# BMS_Main.net
KiCad netlist of a schematic drawn in Altium Designer
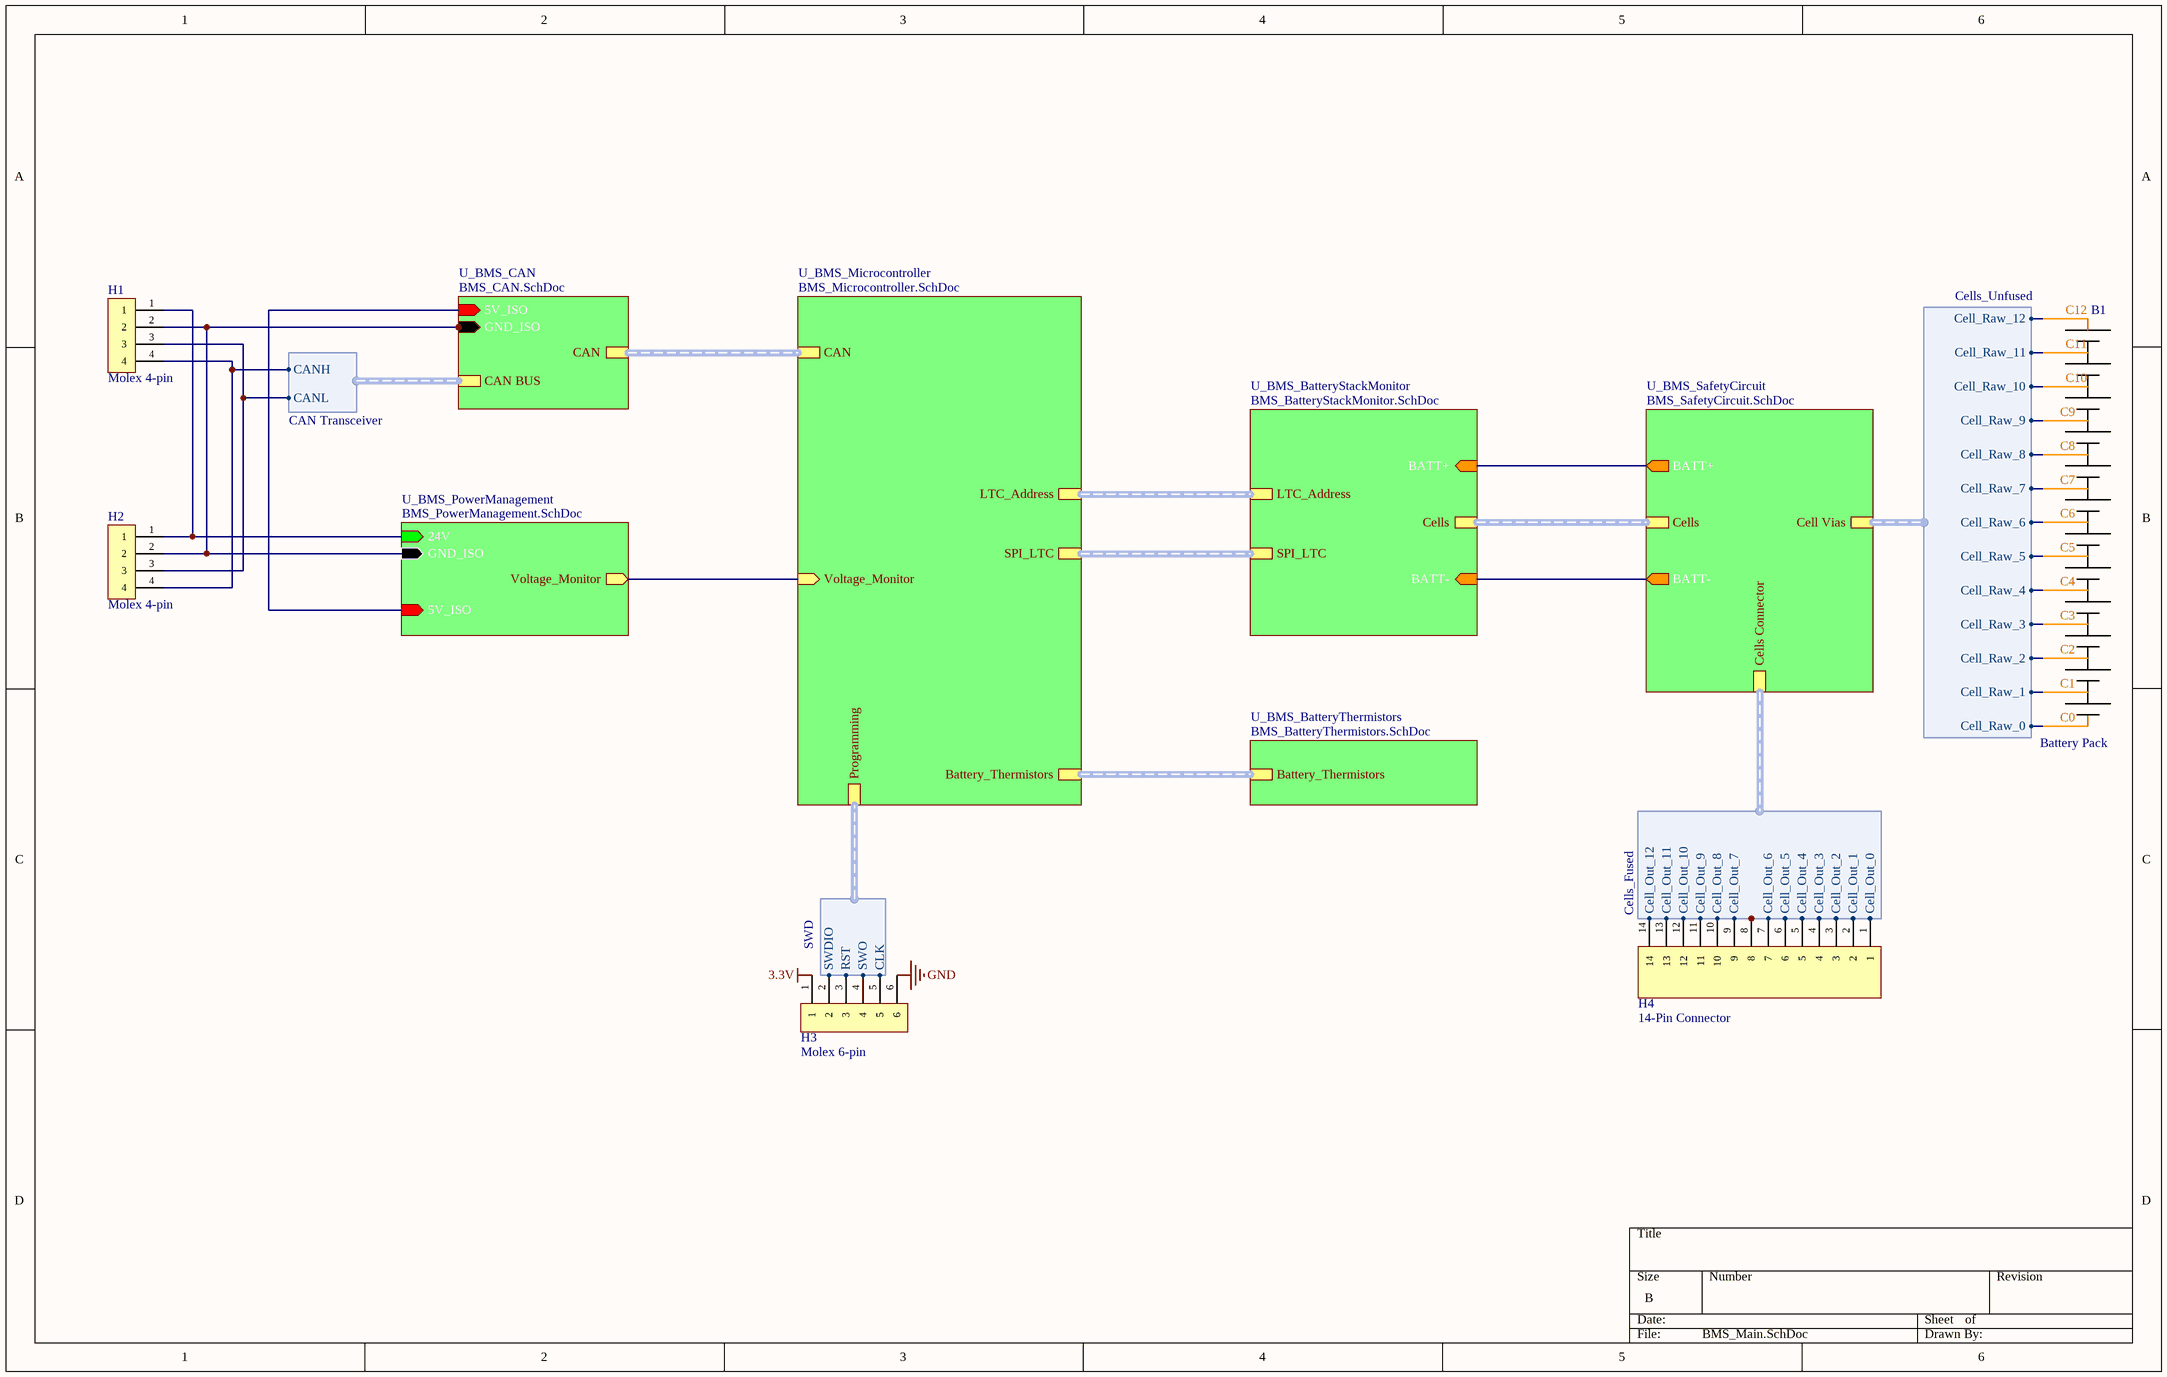
[diagram p0: BMS_Main.SchDoc]

(export (version "E")
  (design (tool "Eeschema 10.0.6"))
  (components
    (comp (ref "B1")
      (value "Battery Pack")
      (footprint "Cells")
      (description "12s3p battery pack, LiFePO4 GH Battery Cell with 3.7V and 8Ah")
      (libsource (lib "BatteryPack") (part "Battery Pack"))
    )
    (comp (ref "H1")
      (value "Molex 4-pin")
      (footprint "Communication Connector")
      (libsource (lib "Molex_4-pin") (part "Molex 4-pin"))
    )
    (comp (ref "H2")
      (value "Molex 4-pin")
      (footprint "Communication Connector")
      (libsource (lib "Molex_4-pin") (part "Molex 4-pin"))
    )
    (comp (ref "H3")
      (value "Molex 6-pin")
      (footprint "ProgrammingConnector")
      (libsource (lib "Molex 6-pin") (part "Molex 6-pin"))
    )
    (comp (ref "H4")
      (value "14-Pin Connector")
      (footprint "CellConnector")
      (libsource (lib "MolexMicroFit_14-pin") (part "14-Pin Connector"))
    )
  )
  (nets
    (net (code "7") (name "/24V") (class "Default")
      (node (ref "H1") (pin "1") (pinfunction "1_1") (pintype "passive"))
      (node (ref "H2") (pin "1") (pinfunction "1_1") (pintype "passive"))
    )
    (net (code "11") (name "/CANH") (class "Default")
      (node (ref "H1") (pin "4") (pinfunction "4_4") (pintype "passive"))
      (node (ref "H2") (pin "4") (pinfunction "4_4") (pintype "passive"))
    )
    (net (code "12") (name "/CANL") (class "Default")
      (node (ref "H1") (pin "3") (pinfunction "3_3") (pintype "passive"))
      (node (ref "H2") (pin "3") (pinfunction "3_3") (pintype "passive"))
    )
    (net (code "14") (name "/CLK") (class "Default")
      (node (ref "H3") (pin "5") (pinfunction "5_5") (pintype "passive"))
    )
    (net (code "15") (name "/Cell_Out_0") (class "Default")
      (node (ref "H4") (pin "1") (pinfunction "1_1") (pintype "passive"))
    )
    (net (code "16") (name "/Cell_Out_1") (class "Default")
      (node (ref "H4") (pin "2") (pinfunction "2_2") (pintype "passive"))
    )
    (net (code "17") (name "/Cell_Out_2") (class "Default")
      (node (ref "H4") (pin "3") (pinfunction "3_3") (pintype "passive"))
    )
    (net (code "18") (name "/Cell_Out_3") (class "Default")
      (node (ref "H4") (pin "4") (pinfunction "4_4") (pintype "passive"))
    )
    (net (code "19") (name "/Cell_Out_4") (class "Default")
      (node (ref "H4") (pin "5") (pinfunction "5_5") (pintype "passive"))
    )
    (net (code "20") (name "/Cell_Out_5") (class "Default")
      (node (ref "H4") (pin "6") (pinfunction "6_6") (pintype "passive"))
    )
    (net (code "21") (name "/Cell_Out_6") (class "Default")
      (node (ref "H4") (pin "7") (pinfunction "7_7") (pintype "passive"))
      (node (ref "H4") (pin "8") (pinfunction "8_8") (pintype "passive"))
    )
    (net (code "22") (name "/Cell_Out_7") (class "Default")
      (node (ref "H4") (pin "9") (pinfunction "9_9") (pintype "passive"))
    )
    (net (code "23") (name "/Cell_Out_8") (class "Default")
      (node (ref "H4") (pin "10") (pinfunction "10_10") (pintype "passive"))
    )
    (net (code "24") (name "/Cell_Out_9") (class "Default")
      (node (ref "H4") (pin "11") (pinfunction "11_11") (pintype "passive"))
    )
    (net (code "25") (name "/Cell_Out_10") (class "Default")
      (node (ref "H4") (pin "12") (pinfunction "12_12") (pintype "passive"))
    )
    (net (code "26") (name "/Cell_Out_11") (class "Default")
      (node (ref "H4") (pin "13") (pinfunction "13_13") (pintype "passive"))
    )
    (net (code "27") (name "/Cell_Out_12") (class "Default")
      (node (ref "H4") (pin "14") (pinfunction "14_14") (pintype "passive"))
    )
    (net (code "42") (name "/GND_ISO") (class "Default")
      (node (ref "H1") (pin "2") (pinfunction "2_2") (pintype "passive"))
      (node (ref "H2") (pin "2") (pinfunction "2_2") (pintype "passive"))
    )
    (net (code "44") (name "/RST") (class "Default")
      (node (ref "H3") (pin "3") (pinfunction "3_3") (pintype "passive"))
    )
    (net (code "46") (name "/SWDIO") (class "Default")
      (node (ref "H3") (pin "2") (pinfunction "2_2") (pintype "passive"))
    )
    (net (code "47") (name "/SWO") (class "Default")
      (node (ref "H3") (pin "4") (pinfunction "4_4") (pintype "passive"))
    )
    (net (code "53") (name "3.3V") (class "Default")
      (node (ref "H3") (pin "1") (pinfunction "1_1") (pintype "passive"))
    )
    (net (code "54") (name "GND") (class "Default")
      (node (ref "H3") (pin "6") (pinfunction "6_6") (pintype "passive"))
    )
    (net (code "55") (name "unconnected-(B1-Pad0)") (class "Default")
      (node (ref "B1") (pin "0") (pinfunction "0_0") (pintype "passive"))
    )
    (net (code "56") (name "unconnected-(B1-Pad1)") (class "Default")
      (node (ref "B1") (pin "1") (pinfunction "1_1") (pintype "passive"))
    )
    (net (code "57") (name "unconnected-(B1-Pad2)") (class "Default")
      (node (ref "B1") (pin "2") (pinfunction "2_2") (pintype "passive"))
    )
    (net (code "58") (name "unconnected-(B1-Pad3)") (class "Default")
      (node (ref "B1") (pin "3") (pinfunction "3_3") (pintype "passive"))
    )
    (net (code "59") (name "unconnected-(B1-Pad4)") (class "Default")
      (node (ref "B1") (pin "4") (pinfunction "4_4") (pintype "passive"))
    )
    (net (code "60") (name "unconnected-(B1-Pad5)") (class "Default")
      (node (ref "B1") (pin "5") (pinfunction "5_5") (pintype "passive"))
    )
    (net (code "61") (name "unconnected-(B1-Pad6)") (class "Default")
      (node (ref "B1") (pin "6") (pinfunction "6_6") (pintype "passive"))
    )
    (net (code "62") (name "unconnected-(B1-Pad7)") (class "Default")
      (node (ref "B1") (pin "7") (pinfunction "7_7") (pintype "passive"))
    )
    (net (code "63") (name "unconnected-(B1-Pad8)") (class "Default")
      (node (ref "B1") (pin "8") (pinfunction "8_8") (pintype "passive"))
    )
    (net (code "64") (name "unconnected-(B1-Pad9)") (class "Default")
      (node (ref "B1") (pin "9") (pinfunction "9_9") (pintype "passive"))
    )
    (net (code "65") (name "unconnected-(B1-Pad10)") (class "Default")
      (node (ref "B1") (pin "10") (pinfunction "10_10") (pintype "passive"))
    )
    (net (code "66") (name "unconnected-(B1-Pad11)") (class "Default")
      (node (ref "B1") (pin "11") (pinfunction "11_11") (pintype "passive"))
    )
    (net (code "67") (name "unconnected-(B1-Pad12)") (class "Default")
      (node (ref "B1") (pin "12") (pinfunction "12_12") (pintype "passive"))
    )
  )
)
